# rev1.net
KiCad netlist of a schematic drawn in EAGLE
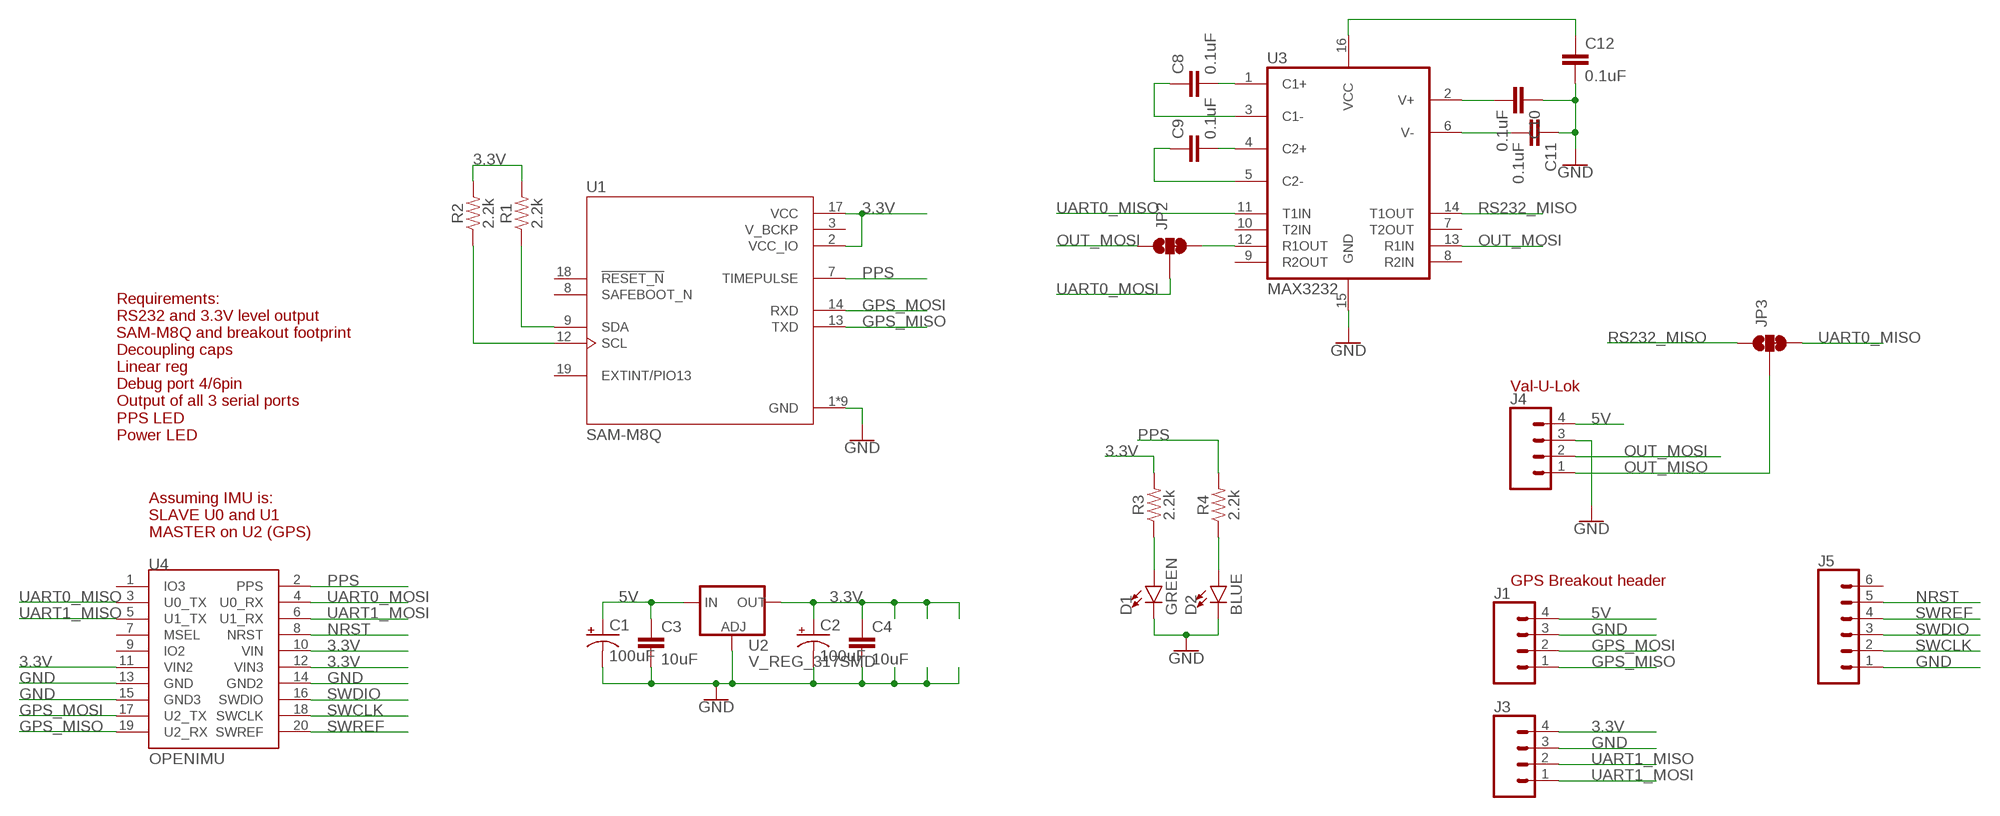
[diagram p0: schematic, sheet 1]

(export (version "E")
  (design (tool "Eeschema 10.0.6"))
  (components
    (comp (ref "C1")
      (value "100uF")
      (footprint "eagle-import:EIA3528")
      (libsource (lib "eagle-import") (part "47UF-POLAR-EIA3528-10V-10%"))
    )
    (comp (ref "C2")
      (value "100uF")
      (footprint "eagle-import:EIA3528")
      (libsource (lib "eagle-import") (part "47UF-POLAR-EIA3528-10V-10%"))
    )
    (comp (ref "C3")
      (value "10uF")
      (footprint "eagle-import:0805")
      (libsource (lib "eagle-import") (part "10UF-0805-10V-10%"))
    )
    (comp (ref "C4")
      (value "10uF")
      (footprint "eagle-import:0805")
      (libsource (lib "eagle-import") (part "10UF-0805-10V-10%"))
    )
    (comp (ref "C8")
      (value "0.1uF")
      (footprint "eagle-import:0603")
      (libsource (lib "eagle-import") (part "0.1UF-0603-25V-5%"))
    )
    (comp (ref "C9")
      (value "0.1uF")
      (footprint "eagle-import:0603")
      (libsource (lib "eagle-import") (part "0.1UF-0603-25V-5%"))
    )
    (comp (ref "C10")
      (value "0.1uF")
      (footprint "eagle-import:0603")
      (libsource (lib "eagle-import") (part "0.1UF-0603-25V-5%"))
    )
    (comp (ref "C11")
      (value "0.1uF")
      (footprint "eagle-import:0603")
      (libsource (lib "eagle-import") (part "0.1UF-0603-25V-5%"))
    )
    (comp (ref "C12")
      (value "0.1uF")
      (footprint "eagle-import:0603")
      (libsource (lib "eagle-import") (part "0.1UF-0603-25V-5%"))
    )
    (comp (ref "D1")
      (value "GREEN")
      (footprint "eagle-import:LED-0603")
      (libsource (lib "eagle-import") (part "LED-GREEN0603"))
    )
    (comp (ref "D2")
      (value "BLUE")
      (footprint "eagle-import:LED-0603")
      (libsource (lib "eagle-import") (part "LED-BLUE0603"))
    )
    (comp (ref "J1")
      (value "CONN_04")
      (footprint "eagle-import:1X04")
      (libsource (lib "eagle-import") (part "CONN_04"))
    )
    (comp (ref "J3")
      (value "CONN_04")
      (footprint "eagle-import:1X04")
      (libsource (lib "eagle-import") (part "CONN_04"))
    )
    (comp (ref "J4")
      (value "CONN_04POLAR")
      (footprint "eagle-import:MOLEX-1X4")
      (libsource (lib "eagle-import") (part "CONN_04POLAR"))
    )
    (comp (ref "J5")
      (value "CONN_06POLAR")
      (footprint "eagle-import:MOLEX-1X6")
      (libsource (lib "eagle-import") (part "CONN_06POLAR"))
    )
    (comp (ref "JP2")
      (value "JUMPER-SMT_3_1-NC_TRACE_SILK")
      (footprint "eagle-import:SMT-JUMPER_3_1-NC_TRACE_SILK")
      (libsource (lib "eagle-import") (part "JUMPER-SMT_3_1-NC_TRACE_SILK"))
    )
    (comp (ref "JP3")
      (value "JUMPER-SMT_3_1-NC_TRACE_SILK")
      (footprint "eagle-import:SMT-JUMPER_3_1-NC_TRACE_SILK")
      (libsource (lib "eagle-import") (part "JUMPER-SMT_3_1-NC_TRACE_SILK"))
    )
    (comp (ref "R1")
      (value "2.2k")
      (footprint "eagle-import:0603")
      (libsource (lib "eagle-import") (part "2.2KOHM-0603-1/10W-1%"))
    )
    (comp (ref "R2")
      (value "2.2k")
      (footprint "eagle-import:0603")
      (libsource (lib "eagle-import") (part "2.2KOHM-0603-1/10W-1%"))
    )
    (comp (ref "R3")
      (value "2.2k")
      (footprint "eagle-import:0603")
      (libsource (lib "eagle-import") (part "2.2KOHM-0603-1/10W-1%"))
    )
    (comp (ref "R4")
      (value "2.2k")
      (footprint "eagle-import:0603")
      (libsource (lib "eagle-import") (part "2.2KOHM-0603-1/10W-1%"))
    )
    (comp (ref "U1")
      (value "SAM-M8Q")
      (footprint "eagle-import:XCVR_SAM-M8Q")
      (fields (field (name "MF") "U-Blox America"))
      (libsource (lib "eagle-import") (part "SAM-M8Q"))
    )
    (comp (ref "U2")
      (value "V_REG_317SMD")
      (footprint "eagle-import:SOT223")
      (libsource (lib "eagle-import") (part "V_REG_317SMD"))
    )
    (comp (ref "U3")
      (value "MAX3232")
      (footprint "eagle-import:TSSOP16")
      (libsource (lib "eagle-import") (part "MAX2323TSSOP"))
    )
    (comp (ref "U4")
      (value "OPENIMU")
      (footprint "eagle-import:OPENIMU300ZA")
      (libsource (lib "eagle-import") (part "OPENIMU"))
    )
  )
  (nets
    (net (code "1") (name "/3.3V") (class "Default")
      (node (ref "C2") (pin "A") (pinfunction "+_A") (pintype "passive"))
      (node (ref "C4") (pin "1") (pinfunction "1_1") (pintype "passive"))
      (node (ref "J3") (pin "4") (pinfunction "4_4") (pintype "passive"))
      (node (ref "R1") (pin "2") (pinfunction "2_2") (pintype "passive"))
      (node (ref "R2") (pin "2") (pinfunction "2_2") (pintype "passive"))
      (node (ref "R3") (pin "2") (pinfunction "2_2") (pintype "passive"))
      (node (ref "U1") (pin "17") (pinfunction "VCC_17") (pintype "power_in"))
      (node (ref "U1") (pin "2") (pinfunction "VCC_IO_2") (pintype "power_in"))
      (node (ref "U2") (pin "2") (pinfunction "OUT_2") (pintype "output"))
      (node (ref "U4") (pin "10") (pinfunction "VIN_10") (pintype "bidirectional"))
      (node (ref "U4") (pin "11") (pinfunction "VIN2_11") (pintype "bidirectional"))
      (node (ref "U4") (pin "12") (pinfunction "VIN3_12") (pintype "bidirectional"))
    )
    (net (code "2") (name "/5V") (class "Default")
      (node (ref "C1") (pin "A") (pinfunction "+_A") (pintype "passive"))
      (node (ref "C3") (pin "1") (pinfunction "1_1") (pintype "passive"))
      (node (ref "J1") (pin "4") (pinfunction "4_4") (pintype "passive"))
      (node (ref "J4") (pin "4") (pinfunction "4_4") (pintype "passive"))
      (node (ref "U2") (pin "3") (pinfunction "IN_3") (pintype "input"))
    )
    (net (code "3") (name "/GPS_MISO") (class "Default")
      (node (ref "J1") (pin "1") (pinfunction "1_1") (pintype "passive"))
      (node (ref "U1") (pin "13") (pinfunction "TXD_13") (pintype "output"))
      (node (ref "U4") (pin "19") (pinfunction "U2_RX_19") (pintype "bidirectional"))
    )
    (net (code "4") (name "/GPS_MOSI") (class "Default")
      (node (ref "J1") (pin "2") (pinfunction "2_2") (pintype "passive"))
      (node (ref "U1") (pin "14") (pinfunction "RXD_14") (pintype "input"))
      (node (ref "U4") (pin "17") (pinfunction "U2_TX_17") (pintype "bidirectional"))
    )
    (net (code "5") (name "/NRST") (class "Default")
      (node (ref "J5") (pin "5") (pinfunction "5_5") (pintype "passive"))
      (node (ref "U4") (pin "8") (pinfunction "NRST_8") (pintype "bidirectional"))
    )
    (net (code "6") (name "/OUT_MISO") (class "Default")
      (node (ref "J4") (pin "1") (pinfunction "1_1") (pintype "passive"))
      (node (ref "JP3") (pin "2") (pinfunction "2_2") (pintype "passive"))
    )
    (net (code "7") (name "/OUT_MOSI") (class "Default")
      (node (ref "J4") (pin "2") (pinfunction "2_2") (pintype "passive"))
      (node (ref "JP2") (pin "1") (pinfunction "1_1") (pintype "passive"))
      (node (ref "U3") (pin "13") (pinfunction "R1IN_13") (pintype "input"))
    )
    (net (code "8") (name "/PPS") (class "Default")
      (node (ref "R4") (pin "2") (pinfunction "2_2") (pintype "passive"))
      (node (ref "U1") (pin "7") (pinfunction "TIMEPULSE_7") (pintype "output"))
      (node (ref "U4") (pin "2") (pinfunction "PPS_2") (pintype "bidirectional"))
    )
    (net (code "9") (name "/RS232_MISO") (class "Default")
      (node (ref "JP3") (pin "1") (pinfunction "1_1") (pintype "passive"))
      (node (ref "U3") (pin "14") (pinfunction "T1OUT_14") (pintype "output"))
    )
    (net (code "10") (name "/SWCLK") (class "Default")
      (node (ref "J5") (pin "2") (pinfunction "2_2") (pintype "passive"))
      (node (ref "U4") (pin "18") (pinfunction "SWCLK_18") (pintype "bidirectional"))
    )
    (net (code "11") (name "/SWDIO") (class "Default")
      (node (ref "J5") (pin "3") (pinfunction "3_3") (pintype "passive"))
      (node (ref "U4") (pin "16") (pinfunction "SWDIO_16") (pintype "bidirectional"))
    )
    (net (code "12") (name "/SWREF") (class "Default")
      (node (ref "J5") (pin "4") (pinfunction "4_4") (pintype "passive"))
      (node (ref "U4") (pin "20") (pinfunction "SWREF_20") (pintype "bidirectional"))
    )
    (net (code "13") (name "/UART0_MISO") (class "Default")
      (node (ref "JP3") (pin "3") (pinfunction "3_3") (pintype "passive"))
      (node (ref "U3") (pin "11") (pinfunction "T1IN_11") (pintype "input"))
      (node (ref "U4") (pin "3") (pinfunction "U0_TX_3") (pintype "bidirectional"))
    )
    (net (code "14") (name "/UART0_MOSI") (class "Default")
      (node (ref "JP2") (pin "2") (pinfunction "2_2") (pintype "passive"))
      (node (ref "U4") (pin "4") (pinfunction "U0_RX_4") (pintype "bidirectional"))
    )
    (net (code "15") (name "/UART1_MISO") (class "Default")
      (node (ref "J3") (pin "2") (pinfunction "2_2") (pintype "passive"))
      (node (ref "U4") (pin "5") (pinfunction "U1_TX_5") (pintype "bidirectional"))
    )
    (net (code "16") (name "/UART1_MOSI") (class "Default")
      (node (ref "J3") (pin "1") (pinfunction "1_1") (pintype "passive"))
      (node (ref "U4") (pin "6") (pinfunction "U1_RX_6") (pintype "bidirectional"))
    )
    (net (code "17") (name "/V_BCKP") (class "Default")
      (node (ref "U1") (pin "3") (pinfunction "V_BCKP_3") (pintype "power_in"))
    )
    (net (code "18") (name "GND") (class "Default")
      (node (ref "C1") (pin "C") (pinfunction "-_C") (pintype "passive"))
      (node (ref "C10") (pin "1") (pinfunction "1_1") (pintype "passive"))
      (node (ref "C11") (pin "1") (pinfunction "1_1") (pintype "passive"))
      (node (ref "C12") (pin "2") (pinfunction "2_2") (pintype "passive"))
      (node (ref "C2") (pin "C") (pinfunction "-_C") (pintype "passive"))
      (node (ref "C3") (pin "2") (pinfunction "2_2") (pintype "passive"))
      (node (ref "C4") (pin "2") (pinfunction "2_2") (pintype "passive"))
      (node (ref "D1") (pin "C") (pinfunction "C_C") (pintype "passive"))
      (node (ref "D2") (pin "C") (pinfunction "C_C") (pintype "passive"))
      (node (ref "J1") (pin "3") (pinfunction "3_3") (pintype "passive"))
      (node (ref "J3") (pin "3") (pinfunction "3_3") (pintype "passive"))
      (node (ref "J4") (pin "3") (pinfunction "3_3") (pintype "passive"))
      (node (ref "J5") (pin "1") (pinfunction "1_1") (pintype "passive"))
      (node (ref "U1") (pin "1") (pinfunction "GND_1") (pintype "power_in"))
      (node (ref "U1") (pin "10") (pinfunction "GND_10") (pintype "power_in"))
      (node (ref "U1") (pin "11") (pinfunction "GND_11") (pintype "power_in"))
      (node (ref "U1") (pin "15") (pinfunction "GND_15") (pintype "power_in"))
      (node (ref "U1") (pin "16") (pinfunction "GND_16") (pintype "power_in"))
      (node (ref "U1") (pin "20") (pinfunction "GND_20") (pintype "power_in"))
      (node (ref "U1") (pin "4") (pinfunction "GND_4") (pintype "power_in"))
      (node (ref "U1") (pin "5") (pinfunction "GND_5") (pintype "power_in"))
      (node (ref "U1") (pin "6") (pinfunction "GND_6") (pintype "power_in"))
      (node (ref "U2") (pin "1") (pinfunction "ADJ_1") (pintype "input"))
      (node (ref "U3") (pin "15") (pinfunction "GND_15") (pintype "bidirectional"))
      (node (ref "U4") (pin "13") (pinfunction "GND_13") (pintype "bidirectional"))
      (node (ref "U4") (pin "14") (pinfunction "GND2_14") (pintype "bidirectional"))
      (node (ref "U4") (pin "15") (pinfunction "GND3_15") (pintype "bidirectional"))
    )
    (net (code "19") (name "Net-(D1-PadA)") (class "Default")
      (node (ref "D1") (pin "A") (pinfunction "A_A") (pintype "passive"))
      (node (ref "R3") (pin "1") (pinfunction "1_1") (pintype "passive"))
    )
    (net (code "20") (name "Net-(D2-PadA)") (class "Default")
      (node (ref "D2") (pin "A") (pinfunction "A_A") (pintype "passive"))
      (node (ref "R4") (pin "1") (pinfunction "1_1") (pintype "passive"))
    )
    (net (code "21") (name "Net-(U1-SCL)") (class "Default")
      (node (ref "R2") (pin "1") (pinfunction "1_1") (pintype "passive"))
      (node (ref "U1") (pin "12") (pinfunction "SCL_12") (pintype "input"))
    )
    (net (code "22") (name "Net-(U1-SDA)") (class "Default")
      (node (ref "R1") (pin "1") (pinfunction "1_1") (pintype "passive"))
      (node (ref "U1") (pin "9") (pinfunction "SDA_9") (pintype "bidirectional"))
    )
    (net (code "23") (name "Net-(U3-C1+)") (class "Default")
      (node (ref "C8") (pin "2") (pinfunction "2_2") (pintype "passive"))
      (node (ref "U3") (pin "1") (pinfunction "C1+_1") (pintype "bidirectional"))
    )
    (net (code "24") (name "Net-(U3-C1-)") (class "Default")
      (node (ref "C8") (pin "1") (pinfunction "1_1") (pintype "passive"))
      (node (ref "U3") (pin "3") (pinfunction "C1-_3") (pintype "bidirectional"))
    )
    (net (code "25") (name "Net-(U3-C2+)") (class "Default")
      (node (ref "C9") (pin "2") (pinfunction "2_2") (pintype "passive"))
      (node (ref "U3") (pin "4") (pinfunction "C2+_4") (pintype "bidirectional"))
    )
    (net (code "26") (name "Net-(U3-C2-)") (class "Default")
      (node (ref "C9") (pin "1") (pinfunction "1_1") (pintype "passive"))
      (node (ref "U3") (pin "5") (pinfunction "C2-_5") (pintype "bidirectional"))
    )
    (net (code "27") (name "Net-(U3-R1OUT)") (class "Default")
      (node (ref "JP2") (pin "3") (pinfunction "3_3") (pintype "passive"))
      (node (ref "U3") (pin "12") (pinfunction "R1OUT_12") (pintype "output"))
    )
    (net (code "28") (name "Net-(U3-V+)") (class "Default")
      (node (ref "C10") (pin "2") (pinfunction "2_2") (pintype "passive"))
      (node (ref "U3") (pin "2") (pinfunction "V+_2") (pintype "bidirectional"))
    )
    (net (code "29") (name "Net-(U3-V-)") (class "Default")
      (node (ref "C11") (pin "2") (pinfunction "2_2") (pintype "passive"))
      (node (ref "U3") (pin "6") (pinfunction "V-_6") (pintype "bidirectional"))
    )
    (net (code "30") (name "Net-(U3-VCC)") (class "Default")
      (node (ref "C12") (pin "1") (pinfunction "1_1") (pintype "passive"))
      (node (ref "U3") (pin "16") (pinfunction "VCC_16") (pintype "bidirectional"))
    )
    (net (code "31") (name "unconnected-(J5-Pad6)") (class "Default")
      (node (ref "J5") (pin "6") (pinfunction "6_6") (pintype "passive"))
    )
    (net (code "32") (name "unconnected-(U1-EXTINT{slash}PIO13-Pad19)") (class "Default")
      (node (ref "U1") (pin "19") (pinfunction "EXTINT/PIO13_19") (pintype "input"))
    )
    (net (code "33") (name "unconnected-(U1-SAFEBOOT_N-Pad8)") (class "Default")
      (node (ref "U1") (pin "8") (pinfunction "SAFEBOOT_N_8") (pintype "input"))
    )
    (net (code "34") (name "unconnected-(U1-~{RESET_N}-Pad18)") (class "Default")
      (node (ref "U1") (pin "18") (pinfunction "~{RESET_N}_18") (pintype "input"))
    )
    (net (code "35") (name "unconnected-(U3-R2IN-Pad8)") (class "Default")
      (node (ref "U3") (pin "8") (pinfunction "R2IN_8") (pintype "input"))
    )
    (net (code "36") (name "unconnected-(U3-R2OUT-Pad9)") (class "Default")
      (node (ref "U3") (pin "9") (pinfunction "R2OUT_9") (pintype "output"))
    )
    (net (code "37") (name "unconnected-(U3-T2IN-Pad10)") (class "Default")
      (node (ref "U3") (pin "10") (pinfunction "T2IN_10") (pintype "input"))
    )
    (net (code "38") (name "unconnected-(U3-T2OUT-Pad7)") (class "Default")
      (node (ref "U3") (pin "7") (pinfunction "T2OUT_7") (pintype "output"))
    )
    (net (code "39") (name "unconnected-(U4-IO2-Pad9)") (class "Default")
      (node (ref "U4") (pin "9") (pinfunction "IO2_9") (pintype "bidirectional"))
    )
    (net (code "40") (name "unconnected-(U4-IO3-Pad1)") (class "Default")
      (node (ref "U4") (pin "1") (pinfunction "IO3_1") (pintype "bidirectional"))
    )
    (net (code "41") (name "unconnected-(U4-MSEL-Pad7)") (class "Default")
      (node (ref "U4") (pin "7") (pinfunction "MSEL_7") (pintype "bidirectional"))
    )
  )
)
